# SolarArray3.net
KiCad netlist of a schematic drawn in Altium Designer
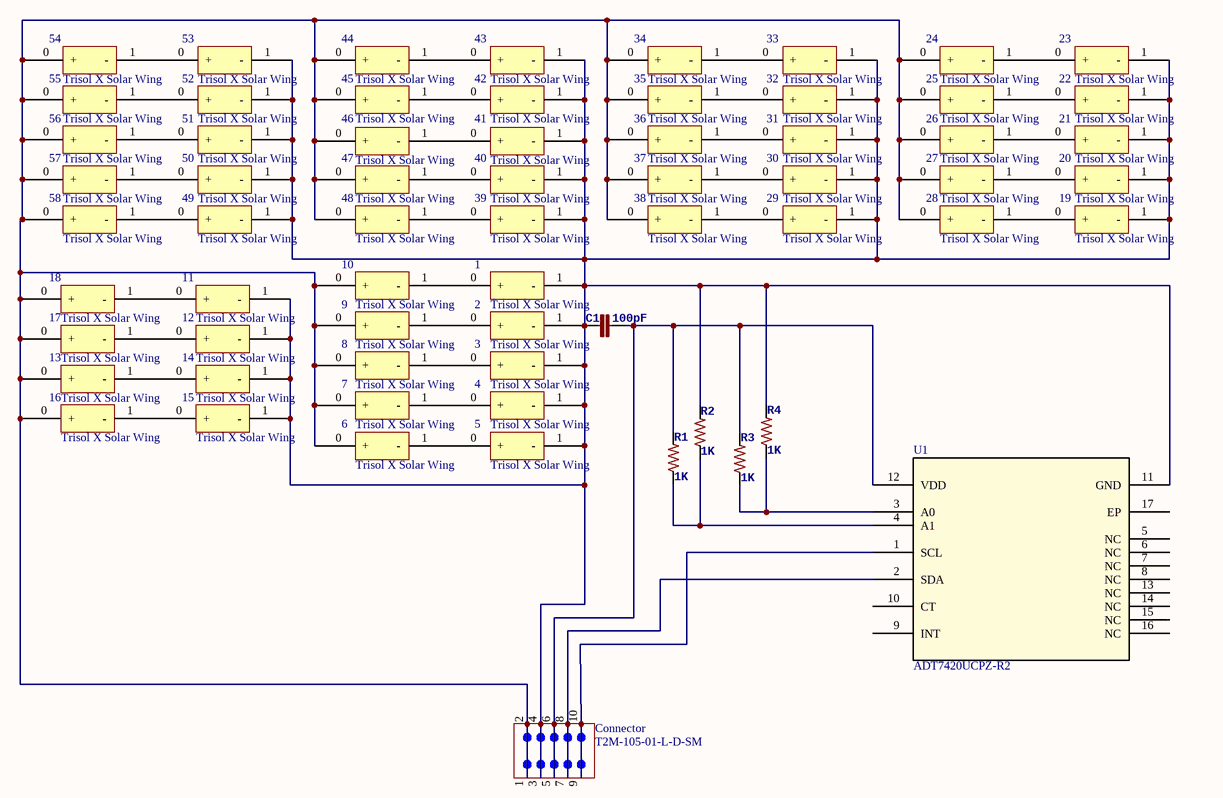
[diagram p0: SolarArray3.SchDoc]

(export (version "E")
  (design (tool "Eeschema 10.0.6"))
  (components
    (comp (ref "1")
      (value "Trisol X Solar Wing")
      (footprint "PCBComponent_1")
      (libsource (lib "CSDCPowerLib") (part "Trisol X Solar Wing"))
    )
    (comp (ref "2")
      (value "Trisol X Solar Wing")
      (footprint "PCBComponent_1")
      (libsource (lib "CSDCPowerLib") (part "Trisol X Solar Wing"))
    )
    (comp (ref "3")
      (value "Trisol X Solar Wing")
      (footprint "PCBComponent_1")
      (libsource (lib "CSDCPowerLib") (part "Trisol X Solar Wing"))
    )
    (comp (ref "4")
      (value "Trisol X Solar Wing")
      (footprint "PCBComponent_1")
      (libsource (lib "CSDCPowerLib") (part "Trisol X Solar Wing"))
    )
    (comp (ref "5")
      (value "Trisol X Solar Wing")
      (footprint "PCBComponent_1")
      (libsource (lib "CSDCPowerLib") (part "Trisol X Solar Wing"))
    )
    (comp (ref "6")
      (value "Trisol X Solar Wing")
      (footprint "PCBComponent_1")
      (libsource (lib "CSDCPowerLib") (part "Trisol X Solar Wing"))
    )
    (comp (ref "7")
      (value "Trisol X Solar Wing")
      (footprint "PCBComponent_1")
      (libsource (lib "CSDCPowerLib") (part "Trisol X Solar Wing"))
    )
    (comp (ref "8")
      (value "Trisol X Solar Wing")
      (footprint "PCBComponent_1")
      (libsource (lib "CSDCPowerLib") (part "Trisol X Solar Wing"))
    )
    (comp (ref "9")
      (value "Trisol X Solar Wing")
      (footprint "PCBComponent_1")
      (libsource (lib "CSDCPowerLib") (part "Trisol X Solar Wing"))
    )
    (comp (ref "10")
      (value "Trisol X Solar Wing")
      (footprint "PCBComponent_1")
      (libsource (lib "CSDCPowerLib") (part "Trisol X Solar Wing"))
    )
    (comp (ref "11")
      (value "Trisol X Solar Wing")
      (footprint "PCBComponent_1")
      (libsource (lib "CSDCPowerLib") (part "Trisol X Solar Wing"))
    )
    (comp (ref "12")
      (value "Trisol X Solar Wing")
      (footprint "PCBComponent_1")
      (libsource (lib "CSDCPowerLib") (part "Trisol X Solar Wing"))
    )
    (comp (ref "13")
      (value "Trisol X Solar Wing")
      (footprint "PCBComponent_1")
      (libsource (lib "CSDCPowerLib") (part "Trisol X Solar Wing"))
    )
    (comp (ref "14")
      (value "Trisol X Solar Wing")
      (footprint "PCBComponent_1")
      (libsource (lib "CSDCPowerLib") (part "Trisol X Solar Wing"))
    )
    (comp (ref "15")
      (value "Trisol X Solar Wing")
      (footprint "PCBComponent_1")
      (libsource (lib "CSDCPowerLib") (part "Trisol X Solar Wing"))
    )
    (comp (ref "16")
      (value "Trisol X Solar Wing")
      (footprint "PCBComponent_1")
      (libsource (lib "CSDCPowerLib") (part "Trisol X Solar Wing"))
    )
    (comp (ref "17")
      (value "Trisol X Solar Wing")
      (footprint "PCBComponent_1")
      (libsource (lib "CSDCPowerLib") (part "Trisol X Solar Wing"))
    )
    (comp (ref "18")
      (value "Trisol X Solar Wing")
      (footprint "PCBComponent_1")
      (libsource (lib "CSDCPowerLib") (part "Trisol X Solar Wing"))
    )
    (comp (ref "19")
      (value "Trisol X Solar Wing")
      (footprint "PCBComponent_1")
      (libsource (lib "CSDCPowerLib") (part "Trisol X Solar Wing"))
    )
    (comp (ref "20")
      (value "Trisol X Solar Wing")
      (footprint "PCBComponent_1")
      (libsource (lib "CSDCPowerLib") (part "Trisol X Solar Wing"))
    )
    (comp (ref "21")
      (value "Trisol X Solar Wing")
      (footprint "PCBComponent_1")
      (libsource (lib "CSDCPowerLib") (part "Trisol X Solar Wing"))
    )
    (comp (ref "22")
      (value "Trisol X Solar Wing")
      (footprint "PCBComponent_1")
      (libsource (lib "CSDCPowerLib") (part "Trisol X Solar Wing"))
    )
    (comp (ref "23")
      (value "Trisol X Solar Wing")
      (footprint "PCBComponent_1")
      (libsource (lib "CSDCPowerLib") (part "Trisol X Solar Wing"))
    )
    (comp (ref "24")
      (value "Trisol X Solar Wing")
      (footprint "PCBComponent_1")
      (libsource (lib "CSDCPowerLib") (part "Trisol X Solar Wing"))
    )
    (comp (ref "25")
      (value "Trisol X Solar Wing")
      (footprint "PCBComponent_1")
      (libsource (lib "CSDCPowerLib") (part "Trisol X Solar Wing"))
    )
    (comp (ref "26")
      (value "Trisol X Solar Wing")
      (footprint "PCBComponent_1")
      (libsource (lib "CSDCPowerLib") (part "Trisol X Solar Wing"))
    )
    (comp (ref "27")
      (value "Trisol X Solar Wing")
      (footprint "PCBComponent_1")
      (libsource (lib "CSDCPowerLib") (part "Trisol X Solar Wing"))
    )
    (comp (ref "28")
      (value "Trisol X Solar Wing")
      (footprint "PCBComponent_1")
      (libsource (lib "CSDCPowerLib") (part "Trisol X Solar Wing"))
    )
    (comp (ref "29")
      (value "Trisol X Solar Wing")
      (footprint "PCBComponent_1")
      (libsource (lib "CSDCPowerLib") (part "Trisol X Solar Wing"))
    )
    (comp (ref "30")
      (value "Trisol X Solar Wing")
      (footprint "PCBComponent_1")
      (libsource (lib "CSDCPowerLib") (part "Trisol X Solar Wing"))
    )
    (comp (ref "31")
      (value "Trisol X Solar Wing")
      (footprint "PCBComponent_1")
      (libsource (lib "CSDCPowerLib") (part "Trisol X Solar Wing"))
    )
    (comp (ref "32")
      (value "Trisol X Solar Wing")
      (footprint "PCBComponent_1")
      (libsource (lib "CSDCPowerLib") (part "Trisol X Solar Wing"))
    )
    (comp (ref "33")
      (value "Trisol X Solar Wing")
      (footprint "PCBComponent_1")
      (libsource (lib "CSDCPowerLib") (part "Trisol X Solar Wing"))
    )
    (comp (ref "34")
      (value "Trisol X Solar Wing")
      (footprint "PCBComponent_1")
      (libsource (lib "CSDCPowerLib") (part "Trisol X Solar Wing"))
    )
    (comp (ref "35")
      (value "Trisol X Solar Wing")
      (footprint "PCBComponent_1")
      (libsource (lib "CSDCPowerLib") (part "Trisol X Solar Wing"))
    )
    (comp (ref "36")
      (value "Trisol X Solar Wing")
      (footprint "PCBComponent_1")
      (libsource (lib "CSDCPowerLib") (part "Trisol X Solar Wing"))
    )
    (comp (ref "37")
      (value "Trisol X Solar Wing")
      (footprint "PCBComponent_1")
      (libsource (lib "CSDCPowerLib") (part "Trisol X Solar Wing"))
    )
    (comp (ref "38")
      (value "Trisol X Solar Wing")
      (footprint "PCBComponent_1")
      (libsource (lib "CSDCPowerLib") (part "Trisol X Solar Wing"))
    )
    (comp (ref "39")
      (value "Trisol X Solar Wing")
      (footprint "PCBComponent_1")
      (libsource (lib "CSDCPowerLib") (part "Trisol X Solar Wing"))
    )
    (comp (ref "40")
      (value "Trisol X Solar Wing")
      (footprint "PCBComponent_1")
      (libsource (lib "CSDCPowerLib") (part "Trisol X Solar Wing"))
    )
    (comp (ref "41")
      (value "Trisol X Solar Wing")
      (footprint "PCBComponent_1")
      (libsource (lib "CSDCPowerLib") (part "Trisol X Solar Wing"))
    )
    (comp (ref "42")
      (value "Trisol X Solar Wing")
      (footprint "PCBComponent_1")
      (libsource (lib "CSDCPowerLib") (part "Trisol X Solar Wing"))
    )
    (comp (ref "43")
      (value "Trisol X Solar Wing")
      (footprint "PCBComponent_1")
      (libsource (lib "CSDCPowerLib") (part "Trisol X Solar Wing"))
    )
    (comp (ref "44")
      (value "Trisol X Solar Wing")
      (footprint "PCBComponent_1")
      (libsource (lib "CSDCPowerLib") (part "Trisol X Solar Wing"))
    )
    (comp (ref "45")
      (value "Trisol X Solar Wing")
      (footprint "PCBComponent_1")
      (libsource (lib "CSDCPowerLib") (part "Trisol X Solar Wing"))
    )
    (comp (ref "46")
      (value "Trisol X Solar Wing")
      (footprint "PCBComponent_1")
      (libsource (lib "CSDCPowerLib") (part "Trisol X Solar Wing"))
    )
    (comp (ref "47")
      (value "Trisol X Solar Wing")
      (footprint "PCBComponent_1")
      (libsource (lib "CSDCPowerLib") (part "Trisol X Solar Wing"))
    )
    (comp (ref "48")
      (value "Trisol X Solar Wing")
      (footprint "PCBComponent_1")
      (libsource (lib "CSDCPowerLib") (part "Trisol X Solar Wing"))
    )
    (comp (ref "49")
      (value "Trisol X Solar Wing")
      (footprint "PCBComponent_1")
      (libsource (lib "CSDCPowerLib") (part "Trisol X Solar Wing"))
    )
    (comp (ref "50")
      (value "Trisol X Solar Wing")
      (footprint "PCBComponent_1")
      (libsource (lib "CSDCPowerLib") (part "Trisol X Solar Wing"))
    )
    (comp (ref "51")
      (value "Trisol X Solar Wing")
      (footprint "PCBComponent_1")
      (libsource (lib "CSDCPowerLib") (part "Trisol X Solar Wing"))
    )
    (comp (ref "52")
      (value "Trisol X Solar Wing")
      (footprint "PCBComponent_1")
      (libsource (lib "CSDCPowerLib") (part "Trisol X Solar Wing"))
    )
    (comp (ref "53")
      (value "Trisol X Solar Wing")
      (footprint "PCBComponent_1")
      (libsource (lib "CSDCPowerLib") (part "Trisol X Solar Wing"))
    )
    (comp (ref "54")
      (value "Trisol X Solar Wing")
      (footprint "PCBComponent_1")
      (libsource (lib "CSDCPowerLib") (part "Trisol X Solar Wing"))
    )
    (comp (ref "55")
      (value "Trisol X Solar Wing")
      (footprint "PCBComponent_1")
      (libsource (lib "CSDCPowerLib") (part "Trisol X Solar Wing"))
    )
    (comp (ref "56")
      (value "Trisol X Solar Wing")
      (footprint "PCBComponent_1")
      (libsource (lib "CSDCPowerLib") (part "Trisol X Solar Wing"))
    )
    (comp (ref "57")
      (value "Trisol X Solar Wing")
      (footprint "PCBComponent_1")
      (libsource (lib "CSDCPowerLib") (part "Trisol X Solar Wing"))
    )
    (comp (ref "58")
      (value "Trisol X Solar Wing")
      (footprint "PCBComponent_1")
      (libsource (lib "CSDCPowerLib") (part "Trisol X Solar Wing"))
    )
    (comp (ref "C1")
      (value "100pF")
      (footprint "0805")
      (fields (field (name "TOLERANCE") "±10%"))
      (libsource (lib "yusend_power") (part "CAP0805_1nF"))
    )
    (comp (ref "Connector")
      (value "T2M-105-01-L-D-SM")
      (footprint "T2M-105-01-X-D-SM")
      (libsource (lib "CSDCPowerLib") (part "T2M-105-01-X-D-SM"))
    )
    (comp (ref "R1")
      (value "1K")
      (footprint "0805")
      (fields
        (field (name "MANUFACTURER") "TE Connectivity")
        (field (name "MANUFACTURER PART NUMBER") "1625856-2")
        (field (name "TOLERANCE") "±10%")
      )
      (libsource (lib "yusend_power") (part "RESISTOR0805-RES_1K"))
    )
    (comp (ref "R2")
      (value "1K")
      (footprint "0805")
      (fields
        (field (name "MANUFACTURER") "TE Connectivity")
        (field (name "MANUFACTURER PART NUMBER") "1625856-2")
        (field (name "TOLERANCE") "±10%")
      )
      (libsource (lib "yusend_power") (part "RESISTOR0805-RES_1K"))
    )
    (comp (ref "R3")
      (value "1K")
      (footprint "0805")
      (fields
        (field (name "MANUFACTURER") "TE Connectivity")
        (field (name "MANUFACTURER PART NUMBER") "1625856-2")
        (field (name "TOLERANCE") "±10%")
      )
      (libsource (lib "yusend_power") (part "RESISTOR0805-RES_1K"))
    )
    (comp (ref "R4")
      (value "1K")
      (footprint "0805")
      (fields
        (field (name "MANUFACTURER") "TE Connectivity")
        (field (name "MANUFACTURER PART NUMBER") "1625856-2")
        (field (name "TOLERANCE") "±10%")
      )
      (libsource (lib "yusend_power") (part "RESISTOR0805-RES_1K"))
    )
    (comp (ref "U1")
      (value "ADT7420UCPZ-R2")
      (footprint "CP_16_17")
      (description "Imported")
      (libsource (lib "Temperature sensor") (part "ADT7420UCPZ-R2"))
    )
  )
  (nets
    (net (code "1") (name "Net-(1-+)") (class "Default")
      (node (ref "1") (pin "0") (pinfunction "+_0") (pintype "passive"))
      (node (ref "10") (pin "1") (pinfunction "-_1") (pintype "passive"))
    )
    (net (code "2") (name "Net-(1--)") (class "Default")
      (node (ref "1") (pin "1") (pinfunction "-_1") (pintype "passive"))
      (node (ref "11") (pin "1") (pinfunction "-_1") (pintype "passive"))
      (node (ref "12") (pin "1") (pinfunction "-_1") (pintype "passive"))
      (node (ref "14") (pin "1") (pinfunction "-_1") (pintype "passive"))
      (node (ref "15") (pin "1") (pinfunction "-_1") (pintype "passive"))
      (node (ref "19") (pin "1") (pinfunction "-_1") (pintype "passive"))
      (node (ref "2") (pin "1") (pinfunction "-_1") (pintype "passive"))
      (node (ref "20") (pin "1") (pinfunction "-_1") (pintype "passive"))
      (node (ref "21") (pin "1") (pinfunction "-_1") (pintype "passive"))
      (node (ref "22") (pin "1") (pinfunction "-_1") (pintype "passive"))
      (node (ref "23") (pin "1") (pinfunction "-_1") (pintype "passive"))
      (node (ref "29") (pin "1") (pinfunction "-_1") (pintype "passive"))
      (node (ref "3") (pin "1") (pinfunction "-_1") (pintype "passive"))
      (node (ref "30") (pin "1") (pinfunction "-_1") (pintype "passive"))
      (node (ref "31") (pin "1") (pinfunction "-_1") (pintype "passive"))
      (node (ref "32") (pin "1") (pinfunction "-_1") (pintype "passive"))
      (node (ref "33") (pin "1") (pinfunction "-_1") (pintype "passive"))
      (node (ref "39") (pin "1") (pinfunction "-_1") (pintype "passive"))
      (node (ref "4") (pin "1") (pinfunction "-_1") (pintype "passive"))
      (node (ref "40") (pin "1") (pinfunction "-_1") (pintype "passive"))
      (node (ref "41") (pin "1") (pinfunction "-_1") (pintype "passive"))
      (node (ref "42") (pin "1") (pinfunction "-_1") (pintype "passive"))
      (node (ref "43") (pin "1") (pinfunction "-_1") (pintype "passive"))
      (node (ref "49") (pin "1") (pinfunction "-_1") (pintype "passive"))
      (node (ref "5") (pin "1") (pinfunction "-_1") (pintype "passive"))
      (node (ref "50") (pin "1") (pinfunction "-_1") (pintype "passive"))
      (node (ref "51") (pin "1") (pinfunction "-_1") (pintype "passive"))
      (node (ref "52") (pin "1") (pinfunction "-_1") (pintype "passive"))
      (node (ref "53") (pin "1") (pinfunction "-_1") (pintype "passive"))
      (node (ref "C1") (pin "1") (pinfunction "1_1") (pintype "passive"))
      (node (ref "Connector") (pin "3") (pinfunction "PINLENGTH=20_3") (pintype "passive"))
      (node (ref "Connector") (pin "4") (pinfunction "PINLENGTH=20_4") (pintype "passive"))
      (node (ref "R2") (pin "2") (pinfunction "2_2") (pintype "passive"))
      (node (ref "R4") (pin "2") (pinfunction "2_2") (pintype "passive"))
      (node (ref "U1") (pin "11") (pinfunction "GND_11") (pintype "passive"))
    )
    (net (code "3") (name "Net-(2-+)") (class "Default")
      (node (ref "2") (pin "0") (pinfunction "+_0") (pintype "passive"))
      (node (ref "9") (pin "1") (pinfunction "-_1") (pintype "passive"))
    )
    (net (code "4") (name "Net-(3-+)") (class "Default")
      (node (ref "3") (pin "0") (pinfunction "+_0") (pintype "passive"))
      (node (ref "8") (pin "1") (pinfunction "-_1") (pintype "passive"))
    )
    (net (code "5") (name "Net-(4-+)") (class "Default")
      (node (ref "4") (pin "0") (pinfunction "+_0") (pintype "passive"))
      (node (ref "7") (pin "1") (pinfunction "-_1") (pintype "passive"))
    )
    (net (code "6") (name "Net-(5-+)") (class "Default")
      (node (ref "5") (pin "0") (pinfunction "+_0") (pintype "passive"))
      (node (ref "6") (pin "1") (pinfunction "-_1") (pintype "passive"))
    )
    (net (code "7") (name "Net-(10-+)") (class "Default")
      (node (ref "10") (pin "0") (pinfunction "+_0") (pintype "passive"))
      (node (ref "13") (pin "0") (pinfunction "+_0") (pintype "passive"))
      (node (ref "16") (pin "0") (pinfunction "+_0") (pintype "passive"))
      (node (ref "17") (pin "0") (pinfunction "+_0") (pintype "passive"))
      (node (ref "18") (pin "0") (pinfunction "+_0") (pintype "passive"))
      (node (ref "24") (pin "0") (pinfunction "+_0") (pintype "passive"))
      (node (ref "25") (pin "0") (pinfunction "+_0") (pintype "passive"))
      (node (ref "26") (pin "0") (pinfunction "+_0") (pintype "passive"))
      (node (ref "27") (pin "0") (pinfunction "+_0") (pintype "passive"))
      (node (ref "28") (pin "0") (pinfunction "+_0") (pintype "passive"))
      (node (ref "34") (pin "0") (pinfunction "+_0") (pintype "passive"))
      (node (ref "35") (pin "0") (pinfunction "+_0") (pintype "passive"))
      (node (ref "36") (pin "0") (pinfunction "+_0") (pintype "passive"))
      (node (ref "37") (pin "0") (pinfunction "+_0") (pintype "passive"))
      (node (ref "38") (pin "0") (pinfunction "+_0") (pintype "passive"))
      (node (ref "44") (pin "0") (pinfunction "+_0") (pintype "passive"))
      (node (ref "45") (pin "0") (pinfunction "+_0") (pintype "passive"))
      (node (ref "46") (pin "0") (pinfunction "+_0") (pintype "passive"))
      (node (ref "47") (pin "0") (pinfunction "+_0") (pintype "passive"))
      (node (ref "48") (pin "0") (pinfunction "+_0") (pintype "passive"))
      (node (ref "54") (pin "0") (pinfunction "+_0") (pintype "passive"))
      (node (ref "55") (pin "0") (pinfunction "+_0") (pintype "passive"))
      (node (ref "56") (pin "0") (pinfunction "+_0") (pintype "passive"))
      (node (ref "57") (pin "0") (pinfunction "+_0") (pintype "passive"))
      (node (ref "58") (pin "0") (pinfunction "+_0") (pintype "passive"))
      (node (ref "6") (pin "0") (pinfunction "+_0") (pintype "passive"))
      (node (ref "7") (pin "0") (pinfunction "+_0") (pintype "passive"))
      (node (ref "8") (pin "0") (pinfunction "+_0") (pintype "passive"))
      (node (ref "9") (pin "0") (pinfunction "+_0") (pintype "passive"))
      (node (ref "Connector") (pin "1") (pinfunction "PINLENGTH=20_1") (pintype "passive"))
      (node (ref "Connector") (pin "2") (pinfunction "PINLENGTH=20_2") (pintype "passive"))
    )
    (net (code "8") (name "Net-(11-+)") (class "Default")
      (node (ref "11") (pin "0") (pinfunction "+_0") (pintype "passive"))
      (node (ref "18") (pin "1") (pinfunction "-_1") (pintype "passive"))
    )
    (net (code "9") (name "Net-(12-+)") (class "Default")
      (node (ref "12") (pin "0") (pinfunction "+_0") (pintype "passive"))
      (node (ref "17") (pin "1") (pinfunction "-_1") (pintype "passive"))
    )
    (net (code "10") (name "Net-(13--)") (class "Default")
      (node (ref "13") (pin "1") (pinfunction "-_1") (pintype "passive"))
      (node (ref "14") (pin "0") (pinfunction "+_0") (pintype "passive"))
    )
    (net (code "11") (name "Net-(15-+)") (class "Default")
      (node (ref "15") (pin "0") (pinfunction "+_0") (pintype "passive"))
      (node (ref "16") (pin "1") (pinfunction "-_1") (pintype "passive"))
    )
    (net (code "12") (name "Net-(19-+)") (class "Default")
      (node (ref "19") (pin "0") (pinfunction "+_0") (pintype "passive"))
      (node (ref "28") (pin "1") (pinfunction "-_1") (pintype "passive"))
    )
    (net (code "13") (name "Net-(20-+)") (class "Default")
      (node (ref "20") (pin "0") (pinfunction "+_0") (pintype "passive"))
      (node (ref "27") (pin "1") (pinfunction "-_1") (pintype "passive"))
    )
    (net (code "14") (name "Net-(21-+)") (class "Default")
      (node (ref "21") (pin "0") (pinfunction "+_0") (pintype "passive"))
      (node (ref "26") (pin "1") (pinfunction "-_1") (pintype "passive"))
    )
    (net (code "15") (name "Net-(22-+)") (class "Default")
      (node (ref "22") (pin "0") (pinfunction "+_0") (pintype "passive"))
      (node (ref "25") (pin "1") (pinfunction "-_1") (pintype "passive"))
    )
    (net (code "16") (name "Net-(23-+)") (class "Default")
      (node (ref "23") (pin "0") (pinfunction "+_0") (pintype "passive"))
      (node (ref "24") (pin "1") (pinfunction "-_1") (pintype "passive"))
    )
    (net (code "17") (name "Net-(29-+)") (class "Default")
      (node (ref "29") (pin "0") (pinfunction "+_0") (pintype "passive"))
      (node (ref "38") (pin "1") (pinfunction "-_1") (pintype "passive"))
    )
    (net (code "18") (name "Net-(30-+)") (class "Default")
      (node (ref "30") (pin "0") (pinfunction "+_0") (pintype "passive"))
      (node (ref "37") (pin "1") (pinfunction "-_1") (pintype "passive"))
    )
    (net (code "19") (name "Net-(31-+)") (class "Default")
      (node (ref "31") (pin "0") (pinfunction "+_0") (pintype "passive"))
      (node (ref "36") (pin "1") (pinfunction "-_1") (pintype "passive"))
    )
    (net (code "20") (name "Net-(32-+)") (class "Default")
      (node (ref "32") (pin "0") (pinfunction "+_0") (pintype "passive"))
      (node (ref "35") (pin "1") (pinfunction "-_1") (pintype "passive"))
    )
    (net (code "21") (name "Net-(33-+)") (class "Default")
      (node (ref "33") (pin "0") (pinfunction "+_0") (pintype "passive"))
      (node (ref "34") (pin "1") (pinfunction "-_1") (pintype "passive"))
    )
    (net (code "22") (name "Net-(39-+)") (class "Default")
      (node (ref "39") (pin "0") (pinfunction "+_0") (pintype "passive"))
      (node (ref "48") (pin "1") (pinfunction "-_1") (pintype "passive"))
    )
    (net (code "23") (name "Net-(40-+)") (class "Default")
      (node (ref "40") (pin "0") (pinfunction "+_0") (pintype "passive"))
      (node (ref "47") (pin "1") (pinfunction "-_1") (pintype "passive"))
    )
    (net (code "24") (name "Net-(41-+)") (class "Default")
      (node (ref "41") (pin "0") (pinfunction "+_0") (pintype "passive"))
      (node (ref "46") (pin "1") (pinfunction "-_1") (pintype "passive"))
    )
    (net (code "25") (name "Net-(42-+)") (class "Default")
      (node (ref "42") (pin "0") (pinfunction "+_0") (pintype "passive"))
      (node (ref "45") (pin "1") (pinfunction "-_1") (pintype "passive"))
    )
    (net (code "26") (name "Net-(43-+)") (class "Default")
      (node (ref "43") (pin "0") (pinfunction "+_0") (pintype "passive"))
      (node (ref "44") (pin "1") (pinfunction "-_1") (pintype "passive"))
    )
    (net (code "27") (name "Net-(49-+)") (class "Default")
      (node (ref "49") (pin "0") (pinfunction "+_0") (pintype "passive"))
      (node (ref "58") (pin "1") (pinfunction "-_1") (pintype "passive"))
    )
    (net (code "28") (name "Net-(50-+)") (class "Default")
      (node (ref "50") (pin "0") (pinfunction "+_0") (pintype "passive"))
      (node (ref "57") (pin "1") (pinfunction "-_1") (pintype "passive"))
    )
    (net (code "29") (name "Net-(51-+)") (class "Default")
      (node (ref "51") (pin "0") (pinfunction "+_0") (pintype "passive"))
      (node (ref "56") (pin "1") (pinfunction "-_1") (pintype "passive"))
    )
    (net (code "30") (name "Net-(52-+)") (class "Default")
      (node (ref "52") (pin "0") (pinfunction "+_0") (pintype "passive"))
      (node (ref "55") (pin "1") (pinfunction "-_1") (pintype "passive"))
    )
    (net (code "31") (name "Net-(53-+)") (class "Default")
      (node (ref "53") (pin "0") (pinfunction "+_0") (pintype "passive"))
      (node (ref "54") (pin "1") (pinfunction "-_1") (pintype "passive"))
    )
    (net (code "32") (name "Net-(U1-A0)") (class "Default")
      (node (ref "R3") (pin "1") (pinfunction "1_1") (pintype "passive"))
      (node (ref "R4") (pin "1") (pinfunction "1_1") (pintype "passive"))
      (node (ref "U1") (pin "3") (pinfunction "A0_3") (pintype "passive"))
    )
    (net (code "33") (name "Net-(U1-A1)") (class "Default")
      (node (ref "R1") (pin "1") (pinfunction "1_1") (pintype "passive"))
      (node (ref "R2") (pin "1") (pinfunction "1_1") (pintype "passive"))
      (node (ref "U1") (pin "4") (pinfunction "A1_4") (pintype "passive"))
    )
    (net (code "34") (name "Net-(U1-SCL)") (class "Default")
      (node (ref "Connector") (pin "10") (pinfunction "PINLENGTH=20_10") (pintype "passive"))
      (node (ref "Connector") (pin "9") (pinfunction "PINLENGTH=20_9") (pintype "passive"))
      (node (ref "U1") (pin "1") (pinfunction "SCL_1") (pintype "passive"))
    )
    (net (code "35") (name "Net-(U1-SDA)") (class "Default")
      (node (ref "Connector") (pin "7") (pinfunction "PINLENGTH=20_7") (pintype "passive"))
      (node (ref "Connector") (pin "8") (pinfunction "PINLENGTH=20_8") (pintype "passive"))
      (node (ref "U1") (pin "2") (pinfunction "SDA_2") (pintype "passive"))
    )
    (net (code "36") (name "Net-(U1-VDD)") (class "Default")
      (node (ref "C1") (pin "2") (pinfunction "2_2") (pintype "passive"))
      (node (ref "Connector") (pin "5") (pinfunction "PINLENGTH=20_5") (pintype "passive"))
      (node (ref "Connector") (pin "6") (pinfunction "PINLENGTH=20_6") (pintype "passive"))
      (node (ref "R1") (pin "2") (pinfunction "2_2") (pintype "passive"))
      (node (ref "R3") (pin "2") (pinfunction "2_2") (pintype "passive"))
      (node (ref "U1") (pin "12") (pinfunction "VDD_12") (pintype "passive"))
    )
    (net (code "37") (name "unconnected-(U1-CT-Pad10)") (class "Default")
      (node (ref "U1") (pin "10") (pinfunction "CT_10") (pintype "passive"))
    )
    (net (code "38") (name "unconnected-(U1-EP-Pad17)") (class "Default")
      (node (ref "U1") (pin "17") (pinfunction "EP_17") (pintype "passive"))
    )
    (net (code "39") (name "unconnected-(U1-INT-Pad9)") (class "Default")
      (node (ref "U1") (pin "9") (pinfunction "INT_9") (pintype "passive"))
    )
    (net (code "40") (name "unconnected-(U1-NC-Pad5)") (class "Default")
      (node (ref "U1") (pin "5") (pinfunction "NC_5") (pintype "passive"))
    )
    (net (code "41") (name "unconnected-(U1-NC-Pad6)") (class "Default")
      (node (ref "U1") (pin "6") (pinfunction "NC_6") (pintype "passive"))
    )
    (net (code "42") (name "unconnected-(U1-NC-Pad7)") (class "Default")
      (node (ref "U1") (pin "7") (pinfunction "NC_7") (pintype "passive"))
    )
    (net (code "43") (name "unconnected-(U1-NC-Pad8)") (class "Default")
      (node (ref "U1") (pin "8") (pinfunction "NC_8") (pintype "passive"))
    )
    (net (code "44") (name "unconnected-(U1-NC-Pad13)") (class "Default")
      (node (ref "U1") (pin "13") (pinfunction "NC_13") (pintype "passive"))
    )
    (net (code "45") (name "unconnected-(U1-NC-Pad14)") (class "Default")
      (node (ref "U1") (pin "14") (pinfunction "NC_14") (pintype "passive"))
    )
    (net (code "46") (name "unconnected-(U1-NC-Pad15)") (class "Default")
      (node (ref "U1") (pin "15") (pinfunction "NC_15") (pintype "passive"))
    )
    (net (code "47") (name "unconnected-(U1-NC-Pad16)") (class "Default")
      (node (ref "U1") (pin "16") (pinfunction "NC_16") (pintype "passive"))
    )
  )
)
